# ultimatedrive2_redraw.net
KiCad netlist of a schematic drawn in EAGLE
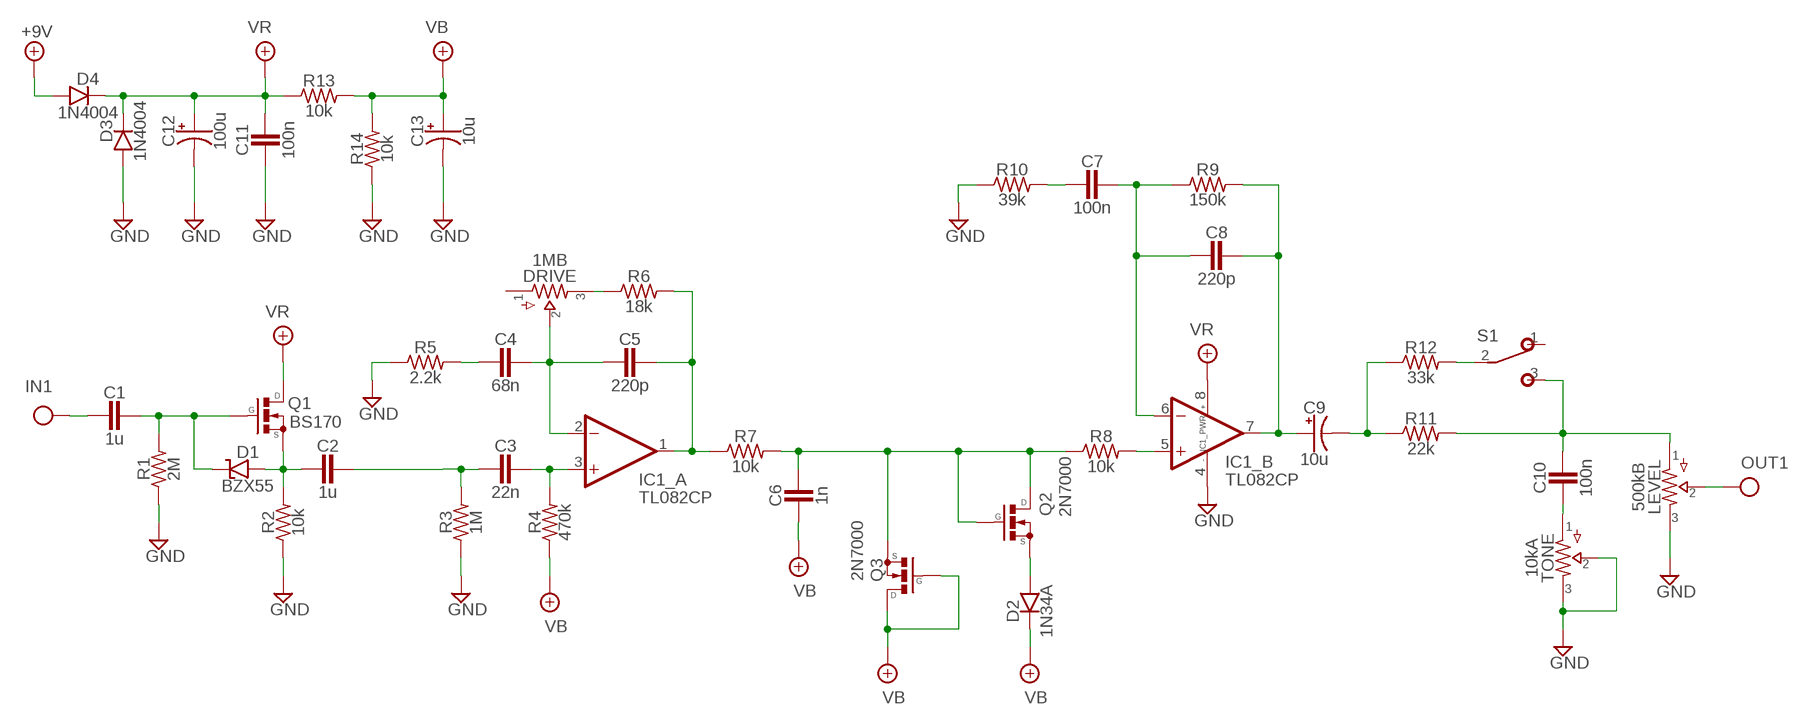
[diagram p0: schematic, sheet 1]

(export (version "E")
  (design (tool "Eeschema 10.0.6"))
  (components
    (comp (ref "C1")
      (value "1u")
      (footprint "eagle-import:BOX_SMALL")
      (libsource (lib "eagle-import") (part "CER/FILMBOX.1"))
    )
    (comp (ref "C2")
      (value "1u")
      (footprint "eagle-import:BOX_SMALL")
      (libsource (lib "eagle-import") (part "CER/FILMBOX.1"))
    )
    (comp (ref "C3")
      (value "22n")
      (footprint "eagle-import:BOX_SMALL")
      (libsource (lib "eagle-import") (part "CER/FILMBOX.1"))
    )
    (comp (ref "C4")
      (value "68n")
      (footprint "eagle-import:BOX_SMALL")
      (libsource (lib "eagle-import") (part "CER/FILMBOX.1"))
    )
    (comp (ref "C5")
      (value "220p")
      (footprint "eagle-import:BOX_SMALL")
      (libsource (lib "eagle-import") (part "CER/FILMBOX.1"))
    )
    (comp (ref "C6")
      (value "1n")
      (footprint "eagle-import:BOX_SMALL")
      (libsource (lib "eagle-import") (part "CER/FILMBOX.1"))
    )
    (comp (ref "C7")
      (value "100n")
      (footprint "eagle-import:BOX_SMALL")
      (libsource (lib "eagle-import") (part "CER/FILMBOX.1"))
    )
    (comp (ref "C8")
      (value "220p")
      (footprint "eagle-import:BOX_SMALL")
      (libsource (lib "eagle-import") (part "CER/FILMBOX.1"))
    )
    (comp (ref "C9")
      (value "10u")
      (footprint "eagle-import:050_020")
      (libsource (lib "eagle-import") (part "0500"))
    )
    (comp (ref "C10")
      (value "100n")
      (footprint "eagle-import:BOX_SMALL")
      (libsource (lib "eagle-import") (part "CER/FILMBOX.1"))
    )
    (comp (ref "C11")
      (value "100n")
      (footprint "eagle-import:BOX_SMALL")
      (libsource (lib "eagle-import") (part "CER/FILMBOX.1"))
    )
    (comp (ref "C12")
      (value "100u")
      (footprint "eagle-import:050_020")
      (libsource (lib "eagle-import") (part "0500"))
    )
    (comp (ref "C13")
      (value "10u")
      (footprint "eagle-import:050_020")
      (libsource (lib "eagle-import") (part "0500"))
    )
    (comp (ref "D1")
      (value "BZX55")
      (footprint "eagle-import:DO41-3")
      (libsource (lib "eagle-import") (part "ZENER.3"))
    )
    (comp (ref "D2")
      (value "1N34A")
      (footprint "eagle-import:DO41-2")
      (libsource (lib "eagle-import") (part "DO41.2"))
    )
    (comp (ref "D3")
      (value "1N4004")
      (footprint "eagle-import:DO41-3")
      (libsource (lib "eagle-import") (part "DO41.3"))
    )
    (comp (ref "D4")
      (value "1N4004")
      (footprint "eagle-import:DO41-3")
      (libsource (lib "eagle-import") (part "DO41.3"))
    )
    (comp (ref "DRIVE")
      (value "1MB")
      (footprint "eagle-import:16MM")
      (libsource (lib "eagle-import") (part "POTS16MM"))
    )
    (comp (ref "IC1")
      (value "TL082CP")
      (footprint "eagle-import:DIL0")
      (libsource (lib "eagle-import") (part "DUALTH"))
    )
    (comp (ref "LEVEL")
      (value "500kB")
      (footprint "eagle-import:16MM")
      (libsource (lib "eagle-import") (part "POTS16MM"))
    )
    (comp (ref "Q1")
      (value "BS170")
      (footprint "eagle-import:SOT54ES")
      (libsource (lib "eagle-import") (part "BS170"))
    )
    (comp (ref "Q2")
      (value "2N7000")
      (footprint "eagle-import:TO92-")
      (libsource (lib "eagle-import") (part "2N7000"))
    )
    (comp (ref "Q3")
      (value "2N7000")
      (footprint "eagle-import:TO92-")
      (libsource (lib "eagle-import") (part "2N7000"))
    )
    (comp (ref "R1")
      (value "2M")
      (footprint "eagle-import:R0207_3")
      (libsource (lib "eagle-import") (part "R_.3B"))
    )
    (comp (ref "R2")
      (value "10k")
      (footprint "eagle-import:R0207_3")
      (libsource (lib "eagle-import") (part "R_.3B"))
    )
    (comp (ref "R3")
      (value "1M")
      (footprint "eagle-import:R0207_3")
      (libsource (lib "eagle-import") (part "R_.3B"))
    )
    (comp (ref "R4")
      (value "470k")
      (footprint "eagle-import:R0207_3")
      (libsource (lib "eagle-import") (part "R_.3B"))
    )
    (comp (ref "R5")
      (value "2.2k")
      (footprint "eagle-import:R0207_3")
      (libsource (lib "eagle-import") (part "R_.3B"))
    )
    (comp (ref "R6")
      (value "18k")
      (footprint "eagle-import:R0207_3")
      (libsource (lib "eagle-import") (part "R_.3B"))
    )
    (comp (ref "R7")
      (value "10k")
      (footprint "eagle-import:R0207_3")
      (libsource (lib "eagle-import") (part "R_.3B"))
    )
    (comp (ref "R8")
      (value "10k")
      (footprint "eagle-import:R0207_3")
      (libsource (lib "eagle-import") (part "R_.3B"))
    )
    (comp (ref "R9")
      (value "150k")
      (footprint "eagle-import:R0207_3")
      (libsource (lib "eagle-import") (part "R_.3B"))
    )
    (comp (ref "R10")
      (value "39k")
      (footprint "eagle-import:R0207_3")
      (libsource (lib "eagle-import") (part "R_.3B"))
    )
    (comp (ref "R11")
      (value "22k")
      (footprint "eagle-import:R0207_3")
      (libsource (lib "eagle-import") (part "R_.3B"))
    )
    (comp (ref "R12")
      (value "33k")
      (footprint "eagle-import:R0207_3")
      (libsource (lib "eagle-import") (part "R_.3B"))
    )
    (comp (ref "R13")
      (value "10k")
      (footprint "eagle-import:R0207_3")
      (libsource (lib "eagle-import") (part "R_.3B"))
    )
    (comp (ref "R14")
      (value "10k")
      (footprint "eagle-import:R0207_3")
      (libsource (lib "eagle-import") (part "R_.3B"))
    )
    (comp (ref "S1")
      (value "SPDT")
      (footprint "eagle-import:M9040P")
      (libsource (lib "eagle-import") (part "SPDT"))
    )
    (comp (ref "TONE")
      (value "10kA")
      (footprint "eagle-import:16MM")
      (libsource (lib "eagle-import") (part "POTS16MM"))
    )
  )
  (nets
    (net (code "1") (name "+9V") (class "Default")
      (node (ref "D4") (pin "A") (pinfunction "A_A") (pintype "passive"))
    )
    (net (code "2") (name "GND") (class "Default")
      (node (ref "C11") (pin "2") (pinfunction "2_2") (pintype "passive"))
      (node (ref "C12") (pin "-") (pinfunction "-_-") (pintype "passive"))
      (node (ref "C13") (pin "-") (pinfunction "-_-") (pintype "passive"))
      (node (ref "D3") (pin "A") (pinfunction "A_A") (pintype "passive"))
      (node (ref "IC1") (pin "4") (pinfunction "V-_4") (pintype "power_in"))
      (node (ref "LEVEL") (pin "3") (pinfunction "3_3") (pintype "passive"))
      (node (ref "R1") (pin "1") (pinfunction "1_1") (pintype "passive"))
      (node (ref "R10") (pin "1") (pinfunction "1_1") (pintype "passive"))
      (node (ref "R14") (pin "1") (pinfunction "1_1") (pintype "passive"))
      (node (ref "R2") (pin "1") (pinfunction "1_1") (pintype "passive"))
      (node (ref "R3") (pin "1") (pinfunction "1_1") (pintype "passive"))
      (node (ref "R5") (pin "1") (pinfunction "1_1") (pintype "passive"))
      (node (ref "TONE") (pin "2") (pinfunction "2_2") (pintype "passive"))
      (node (ref "TONE") (pin "3") (pinfunction "3_3") (pintype "passive"))
    )
    (net (code "3") (name "IN") (class "Default")
      (node (ref "C1") (pin "2") (pinfunction "2_2") (pintype "passive"))
    )
    (net (code "4") (name "Net-(C1-Pad1)") (class "Default")
      (node (ref "C1") (pin "1") (pinfunction "1_1") (pintype "passive"))
      (node (ref "D1") (pin "C") (pinfunction "C_C") (pintype "passive"))
      (node (ref "Q1") (pin "G") (pinfunction "G_G") (pintype "passive"))
      (node (ref "R1") (pin "2") (pinfunction "2_2") (pintype "passive"))
    )
    (net (code "5") (name "Net-(C2-Pad1)") (class "Default")
      (node (ref "C2") (pin "1") (pinfunction "1_1") (pintype "passive"))
      (node (ref "C3") (pin "2") (pinfunction "2_2") (pintype "passive"))
      (node (ref "R3") (pin "2") (pinfunction "2_2") (pintype "passive"))
    )
    (net (code "6") (name "Net-(C2-Pad2)") (class "Default")
      (node (ref "C2") (pin "2") (pinfunction "2_2") (pintype "passive"))
      (node (ref "D1") (pin "A") (pinfunction "A_A") (pintype "passive"))
      (node (ref "Q1") (pin "S") (pinfunction "S_S") (pintype "passive"))
      (node (ref "R2") (pin "2") (pinfunction "2_2") (pintype "passive"))
    )
    (net (code "7") (name "Net-(C4-Pad2)") (class "Default")
      (node (ref "C4") (pin "2") (pinfunction "2_2") (pintype "passive"))
      (node (ref "R5") (pin "2") (pinfunction "2_2") (pintype "passive"))
    )
    (net (code "8") (name "Net-(C7-Pad2)") (class "Default")
      (node (ref "C7") (pin "2") (pinfunction "2_2") (pintype "passive"))
      (node (ref "R10") (pin "2") (pinfunction "2_2") (pintype "passive"))
    )
    (net (code "9") (name "Net-(C9-Pad-)") (class "Default")
      (node (ref "C9") (pin "-") (pinfunction "-_-") (pintype "passive"))
      (node (ref "R11") (pin "1") (pinfunction "1_1") (pintype "passive"))
      (node (ref "R12") (pin "1") (pinfunction "1_1") (pintype "passive"))
    )
    (net (code "10") (name "Net-(C10-Pad2)") (class "Default")
      (node (ref "C10") (pin "2") (pinfunction "2_2") (pintype "passive"))
      (node (ref "TONE") (pin "1") (pinfunction "1_1") (pintype "passive"))
    )
    (net (code "11") (name "Net-(DRIVE-Pad3)") (class "Default")
      (node (ref "DRIVE") (pin "3") (pinfunction "3_3") (pintype "passive"))
      (node (ref "R6") (pin "1") (pinfunction "1_1") (pintype "passive"))
    )
    (net (code "12") (name "Net-(IC1A-+IN)") (class "Default")
      (node (ref "C3") (pin "1") (pinfunction "1_1") (pintype "passive"))
      (node (ref "IC1") (pin "3") (pinfunction "+IN_3") (pintype "input"))
      (node (ref "R4") (pin "2") (pinfunction "2_2") (pintype "passive"))
    )
    (net (code "13") (name "Net-(IC1A--IN)") (class "Default")
      (node (ref "C4") (pin "1") (pinfunction "1_1") (pintype "passive"))
      (node (ref "C5") (pin "2") (pinfunction "2_2") (pintype "passive"))
      (node (ref "DRIVE") (pin "2") (pinfunction "2_2") (pintype "passive"))
      (node (ref "IC1") (pin "2") (pinfunction "-IN_2") (pintype "input"))
    )
    (net (code "14") (name "Net-(IC1A-OUT)") (class "Default")
      (node (ref "C5") (pin "1") (pinfunction "1_1") (pintype "passive"))
      (node (ref "IC1") (pin "1") (pinfunction "OUT_1") (pintype "output"))
      (node (ref "R6") (pin "2") (pinfunction "2_2") (pintype "passive"))
      (node (ref "R7") (pin "1") (pinfunction "1_1") (pintype "passive"))
    )
    (net (code "15") (name "Net-(IC1B-+IN)") (class "Default")
      (node (ref "IC1") (pin "5") (pinfunction "+IN_5") (pintype "input"))
      (node (ref "R8") (pin "2") (pinfunction "2_2") (pintype "passive"))
    )
    (net (code "16") (name "Net-(IC1B--IN)") (class "Default")
      (node (ref "C7") (pin "1") (pinfunction "1_1") (pintype "passive"))
      (node (ref "C8") (pin "2") (pinfunction "2_2") (pintype "passive"))
      (node (ref "IC1") (pin "6") (pinfunction "-IN_6") (pintype "input"))
      (node (ref "R9") (pin "1") (pinfunction "1_1") (pintype "passive"))
    )
    (net (code "17") (name "Net-(IC1B-OUT)") (class "Default")
      (node (ref "C8") (pin "1") (pinfunction "1_1") (pintype "passive"))
      (node (ref "C9") (pin "+") (pinfunction "+_+") (pintype "passive"))
      (node (ref "IC1") (pin "7") (pinfunction "OUT_7") (pintype "output"))
      (node (ref "R9") (pin "2") (pinfunction "2_2") (pintype "passive"))
    )
    (net (code "18") (name "Net-(Q2-D)") (class "Default")
      (node (ref "C6") (pin "1") (pinfunction "1_1") (pintype "passive"))
      (node (ref "Q2") (pin "1") (pinfunction "D_1") (pintype "passive"))
      (node (ref "Q2") (pin "2") (pinfunction "G_2") (pintype "passive"))
      (node (ref "Q3") (pin "3") (pinfunction "S_3") (pintype "passive"))
      (node (ref "R7") (pin "2") (pinfunction "2_2") (pintype "passive"))
      (node (ref "R8") (pin "1") (pinfunction "1_1") (pintype "passive"))
    )
    (net (code "19") (name "Net-(Q2-S)") (class "Default")
      (node (ref "D2") (pin "A") (pinfunction "A_A") (pintype "passive"))
      (node (ref "Q2") (pin "3") (pinfunction "S_3") (pintype "passive"))
    )
    (net (code "20") (name "Net-(S1-P)") (class "Default")
      (node (ref "R12") (pin "2") (pinfunction "2_2") (pintype "passive"))
      (node (ref "S1") (pin "2") (pinfunction "P_2") (pintype "passive"))
    )
    (net (code "21") (name "Net-(S1-S)") (class "Default")
      (node (ref "C10") (pin "1") (pinfunction "1_1") (pintype "passive"))
      (node (ref "LEVEL") (pin "1") (pinfunction "1_1") (pintype "passive"))
      (node (ref "R11") (pin "2") (pinfunction "2_2") (pintype "passive"))
      (node (ref "S1") (pin "3") (pinfunction "S_3") (pintype "passive"))
    )
    (net (code "22") (name "OUT") (class "Default")
      (node (ref "LEVEL") (pin "2") (pinfunction "2_2") (pintype "passive"))
    )
    (net (code "23") (name "VB") (class "Default")
      (node (ref "C13") (pin "+") (pinfunction "+_+") (pintype "passive"))
      (node (ref "C6") (pin "2") (pinfunction "2_2") (pintype "passive"))
      (node (ref "D2") (pin "C") (pinfunction "C_C") (pintype "passive"))
      (node (ref "Q3") (pin "1") (pinfunction "D_1") (pintype "passive"))
      (node (ref "Q3") (pin "2") (pinfunction "G_2") (pintype "passive"))
      (node (ref "R13") (pin "2") (pinfunction "2_2") (pintype "passive"))
      (node (ref "R14") (pin "2") (pinfunction "2_2") (pintype "passive"))
      (node (ref "R4") (pin "1") (pinfunction "1_1") (pintype "passive"))
    )
    (net (code "24") (name "VR") (class "Default")
      (node (ref "C11") (pin "1") (pinfunction "1_1") (pintype "passive"))
      (node (ref "C12") (pin "+") (pinfunction "+_+") (pintype "passive"))
      (node (ref "D3") (pin "C") (pinfunction "C_C") (pintype "passive"))
      (node (ref "D4") (pin "C") (pinfunction "C_C") (pintype "passive"))
      (node (ref "IC1") (pin "8") (pinfunction "V+_8") (pintype "power_in"))
      (node (ref "Q1") (pin "D") (pinfunction "D_D") (pintype "passive"))
      (node (ref "R13") (pin "1") (pinfunction "1_1") (pintype "passive"))
    )
    (net (code "25") (name "unconnected-(DRIVE-Pad1)") (class "Default")
      (node (ref "DRIVE") (pin "1") (pinfunction "1_1") (pintype "passive"))
    )
    (net (code "26") (name "unconnected-(S1-O-Pad1)") (class "Default")
      (node (ref "S1") (pin "1") (pinfunction "O_1") (pintype "passive"))
    )
  )
)
